# TPS74401RGWRM3.net
KiCad netlist of a schematic drawn in Altium Designer
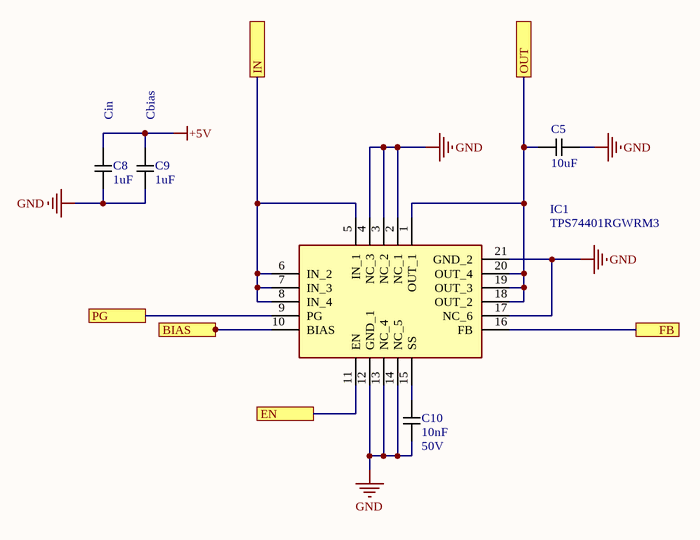
[diagram p0: TPS74401RGWRM3.SchDoc]

(export (version "E")
  (design (tool "Eeschema 10.0.6"))
  (components
    (comp (ref "C5")
      (value "10uF")
      (footprint "C0603_MD")
      (description "CAP CER 10UF 16V 20% X6S 0603")
      (fields (field (name "MANUFACTURER") "Murata Electronics North America") (field (name "VOLTAGE") "16V"))
      (libsource (lib "Capacitor") (part "GRM188C81C106MA73D"))
    )
    (comp (ref "C8")
      (value "Cin")
      (footprint "C0603_MD")
      (description "CAP CER 1UF 50V 10% X5R 0603")
      (fields
        (field (name "MANUFACTURER") "Taiyo Yuden")
        (field (name "VOLTAGE") "50V")
        (field (name "ALTIUM_VALUE") "1uF")
      )
      (libsource (lib "Capacitor") (part "UMK107BJ105KA-T"))
    )
    (comp (ref "C9")
      (value "Cbias")
      (footprint "C0603_MD")
      (description "CAP CER 1UF 50V 10% X5R 0603")
      (fields
        (field (name "MANUFACTURER") "Taiyo Yuden")
        (field (name "VOLTAGE") "50V")
        (field (name "ALTIUM_VALUE") "1uF")
      )
      (libsource (lib "Capacitor") (part "UMK107BJ105KA-T"))
    )
    (comp (ref "C10")
      (value "10nF")
      (footprint "C0603_MD")
      (description "10000pF 50V Ceramic Capacitor X7R 0603")
      (fields
        (field (name "MANUFACTURER") "Samsung Electro-Mechanics America, Inc.")
        (field (name "VOLTAGE") "50V")
        (field (name "Comment") "CL10B103KB8NNNC")
      )
      (libsource (lib "Capacitor") (part "CL10B103KB8NNNC"))
    )
    (comp (ref "IC1")
      (value "TPS74401RGWRM3")
      (footprint "SamacSys:QFN65P500X500X100-21N-D")
      (description "Integrated Circuit")
      (fields (field (name "MOUSER PART NUMBER") "595-TPS74401RGWRM3"))
      (libsource (lib "*") (part "TPS74401RGWRM3"))
    )
  )
  (nets
    (net (code "1") (name "+5V") (class "Default")
      (node (ref "C8") (pin "1") (pinfunction "1_1") (pintype "passive"))
      (node (ref "C9") (pin "1") (pinfunction "1_1") (pintype "passive"))
    )
    (net (code "2") (name "/BIAS") (class "Default")
      (node (ref "IC1") (pin "10") (pinfunction "BIAS_10") (pintype "passive"))
    )
    (net (code "3") (name "/EN") (class "Default")
      (node (ref "IC1") (pin "11") (pinfunction "EN_11") (pintype "passive"))
    )
    (net (code "4") (name "/FB") (class "Default")
      (node (ref "IC1") (pin "16") (pinfunction "FB_16") (pintype "passive"))
    )
    (net (code "5") (name "/IN") (class "Default")
      (node (ref "IC1") (pin "5") (pinfunction "IN_1_5") (pintype "passive"))
      (node (ref "IC1") (pin "6") (pinfunction "IN_2_6") (pintype "passive"))
      (node (ref "IC1") (pin "7") (pinfunction "IN_3_7") (pintype "passive"))
      (node (ref "IC1") (pin "8") (pinfunction "IN_4_8") (pintype "passive"))
    )
    (net (code "6") (name "/OUT") (class "Default")
      (node (ref "C5") (pin "2") (pinfunction "2_2") (pintype "passive"))
      (node (ref "IC1") (pin "1") (pinfunction "OUT_1_1") (pintype "passive"))
      (node (ref "IC1") (pin "18") (pinfunction "OUT_2_18") (pintype "passive"))
      (node (ref "IC1") (pin "19") (pinfunction "OUT_3_19") (pintype "passive"))
      (node (ref "IC1") (pin "20") (pinfunction "OUT_4_20") (pintype "passive"))
    )
    (net (code "7") (name "/PG") (class "Default")
      (node (ref "IC1") (pin "9") (pinfunction "PG_9") (pintype "passive"))
    )
    (net (code "8") (name "GND") (class "Default")
      (node (ref "C10") (pin "2") (pinfunction "2_2") (pintype "passive"))
      (node (ref "C5") (pin "1") (pinfunction "1_1") (pintype "passive"))
      (node (ref "C8") (pin "2") (pinfunction "2_2") (pintype "passive"))
      (node (ref "C9") (pin "2") (pinfunction "2_2") (pintype "passive"))
      (node (ref "IC1") (pin "12") (pinfunction "GND_1_12") (pintype "passive"))
      (node (ref "IC1") (pin "13") (pinfunction "NC_4_13") (pintype "passive"))
      (node (ref "IC1") (pin "14") (pinfunction "NC_5_14") (pintype "passive"))
      (node (ref "IC1") (pin "17") (pinfunction "NC_6_17") (pintype "passive"))
      (node (ref "IC1") (pin "2") (pinfunction "NC_1_2") (pintype "passive"))
      (node (ref "IC1") (pin "21") (pinfunction "GND_2_21") (pintype "passive"))
      (node (ref "IC1") (pin "3") (pinfunction "NC_2_3") (pintype "passive"))
      (node (ref "IC1") (pin "4") (pinfunction "NC_3_4") (pintype "passive"))
    )
    (net (code "9") (name "Net-(IC1-SS)") (class "Default")
      (node (ref "C10") (pin "1") (pinfunction "1_1") (pintype "passive"))
      (node (ref "IC1") (pin "15") (pinfunction "SS_15") (pintype "passive"))
    )
  )
)
